# ir03.net
KiCad netlist of a schematic drawn in EAGLE
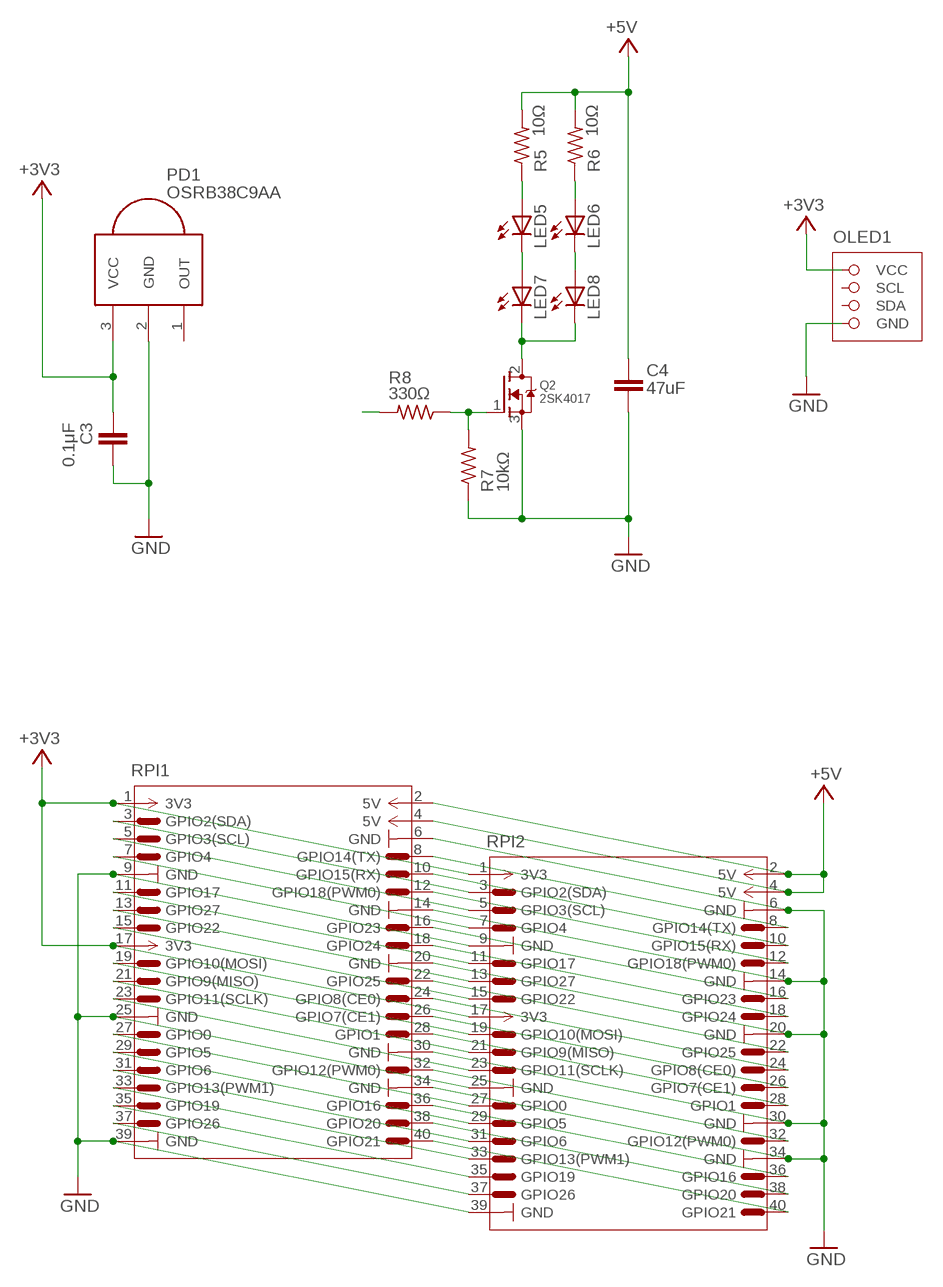
[diagram p0: schematic, sheet 1]

(export (version "E")
  (design (tool "Eeschema 10.0.6"))
  (components
    (comp (ref "C3")
      (value "0.1μF")
      (footprint "eagle-import:C025-025X050")
      (libsource (lib "eagle-import") (part "C-EU025-025X050"))
    )
    (comp (ref "C4")
      (value "47uF")
      (footprint "eagle-import:C025-025X050")
      (libsource (lib "eagle-import") (part "C-EU025-025X050"))
    )
    (comp (ref "LED5")
      (value "LED3MM")
      (footprint "eagle-import:LED3MM")
      (libsource (lib "eagle-import") (part "LED3MM"))
    )
    (comp (ref "LED6")
      (value "LED3MM")
      (footprint "eagle-import:LED3MM")
      (libsource (lib "eagle-import") (part "LED3MM"))
    )
    (comp (ref "LED7")
      (value "LED3MM")
      (footprint "eagle-import:LED3MM")
      (libsource (lib "eagle-import") (part "LED3MM"))
    )
    (comp (ref "LED8")
      (value "LED3MM")
      (footprint "eagle-import:LED3MM")
      (libsource (lib "eagle-import") (part "LED3MM"))
    )
    (comp (ref "OLED1")
      (value "OLED-SSD1306-0.96")
      (footprint "eagle-import:OLED-I2C-0.96")
      (libsource (lib "eagle-import") (part "OLED-SSD1306-0.96"))
    )
    (comp (ref "PD1")
      (value "OSRB38C9AA")
      (footprint "eagle-import:PNA460XM")
      (libsource (lib "eagle-import") (part "PNA460XM"))
    )
    (comp (ref "Q2")
      (value "2SK4017")
      (footprint "eagle-import:TO220V")
      (libsource (lib "eagle-import") (part "MOSFET-NGDS_TO220V"))
    )
    (comp (ref "R5")
      (value "10Ω")
      (footprint "eagle-import:0204_5")
      (libsource (lib "eagle-import") (part "R-US_0204/5"))
    )
    (comp (ref "R6")
      (value "10Ω")
      (footprint "eagle-import:0204_5")
      (libsource (lib "eagle-import") (part "R-US_0204/5"))
    )
    (comp (ref "R7")
      (value "10kΩ")
      (footprint "eagle-import:0204_5")
      (libsource (lib "eagle-import") (part "R-US_0204/5"))
    )
    (comp (ref "R8")
      (value "330Ω")
      (footprint "eagle-import:0204_5")
      (libsource (lib "eagle-import") (part "R-US_0204/5"))
    )
    (comp (ref "RPI1")
      (value "RPI-PIN")
      (footprint "eagle-import:RPI-PIN")
      (libsource (lib "eagle-import") (part "RPI-PIN"))
    )
    (comp (ref "RPI2")
      (value "RPI-PIN")
      (footprint "eagle-import:RPI-PIN")
      (libsource (lib "eagle-import") (part "RPI-PIN"))
    )
  )
  (nets
    (net (code "1") (name "+3V3") (class "Default")
      (node (ref "C3") (pin "1") (pinfunction "1_1") (pintype "passive"))
      (node (ref "OLED1") (pin "VCC") (pinfunction "VCC_VCC") (pintype "bidirectional"))
      (node (ref "PD1") (pin "3") (pinfunction "VCC_3") (pintype "power_in"))
      (node (ref "RPI1") (pin "1") (pinfunction "3V3_1") (pintype "passive"))
      (node (ref "RPI1") (pin "17") (pinfunction "3V3_17") (pintype "passive"))
      (node (ref "RPI2") (pin "1") (pinfunction "3V3_1") (pintype "passive"))
      (node (ref "RPI2") (pin "17") (pinfunction "3V3_17") (pintype "passive"))
    )
    (net (code "2") (name "+5V") (class "Default")
      (node (ref "C4") (pin "1") (pinfunction "1_1") (pintype "passive"))
      (node (ref "R5") (pin "2") (pinfunction "2_2") (pintype "passive"))
      (node (ref "R6") (pin "2") (pinfunction "2_2") (pintype "passive"))
      (node (ref "RPI1") (pin "2") (pinfunction "5V_2") (pintype "passive"))
      (node (ref "RPI1") (pin "4") (pinfunction "5V_4") (pintype "passive"))
      (node (ref "RPI2") (pin "2") (pinfunction "5V_2") (pintype "passive"))
      (node (ref "RPI2") (pin "4") (pinfunction "5V_4") (pintype "passive"))
    )
    (net (code "3") (name "GND") (class "Default")
      (node (ref "C3") (pin "2") (pinfunction "2_2") (pintype "passive"))
      (node (ref "C4") (pin "2") (pinfunction "2_2") (pintype "passive"))
      (node (ref "OLED1") (pin "GND") (pinfunction "GND_GND") (pintype "bidirectional"))
      (node (ref "PD1") (pin "2") (pinfunction "GND_2") (pintype "power_in"))
      (node (ref "Q2") (pin "3") (pinfunction "S_3") (pintype "bidirectional"))
      (node (ref "R7") (pin "1") (pinfunction "1_1") (pintype "passive"))
      (node (ref "RPI1") (pin "14") (pinfunction "GND_14") (pintype "passive"))
      (node (ref "RPI1") (pin "20") (pinfunction "GND_20") (pintype "passive"))
      (node (ref "RPI1") (pin "25") (pinfunction "GND_25") (pintype "passive"))
      (node (ref "RPI1") (pin "30") (pinfunction "GND_30") (pintype "passive"))
      (node (ref "RPI1") (pin "34") (pinfunction "GND_34") (pintype "passive"))
      (node (ref "RPI1") (pin "39") (pinfunction "GND_39") (pintype "passive"))
      (node (ref "RPI1") (pin "6") (pinfunction "GND_6") (pintype "passive"))
      (node (ref "RPI1") (pin "9") (pinfunction "GND_9") (pintype "passive"))
      (node (ref "RPI2") (pin "14") (pinfunction "GND_14") (pintype "passive"))
      (node (ref "RPI2") (pin "20") (pinfunction "GND_20") (pintype "passive"))
      (node (ref "RPI2") (pin "25") (pinfunction "GND_25") (pintype "passive"))
      (node (ref "RPI2") (pin "30") (pinfunction "GND_30") (pintype "passive"))
      (node (ref "RPI2") (pin "34") (pinfunction "GND_34") (pintype "passive"))
      (node (ref "RPI2") (pin "39") (pinfunction "GND_39") (pintype "passive"))
      (node (ref "RPI2") (pin "6") (pinfunction "GND_6") (pintype "passive"))
      (node (ref "RPI2") (pin "9") (pinfunction "GND_9") (pintype "passive"))
    )
    (net (code "4") (name "Net-(LED5-C)") (class "Default")
      (node (ref "LED5") (pin "K") (pinfunction "C_K") (pintype "passive"))
      (node (ref "LED7") (pin "A") (pinfunction "A_A") (pintype "passive"))
    )
    (net (code "5") (name "Net-(LED5-PadA)") (class "Default")
      (node (ref "LED5") (pin "A") (pinfunction "A_A") (pintype "passive"))
      (node (ref "R5") (pin "1") (pinfunction "1_1") (pintype "passive"))
    )
    (net (code "6") (name "Net-(LED6-C)") (class "Default")
      (node (ref "LED6") (pin "K") (pinfunction "C_K") (pintype "passive"))
      (node (ref "LED8") (pin "A") (pinfunction "A_A") (pintype "passive"))
    )
    (net (code "7") (name "Net-(LED6-PadA)") (class "Default")
      (node (ref "LED6") (pin "A") (pinfunction "A_A") (pintype "passive"))
      (node (ref "R6") (pin "1") (pinfunction "1_1") (pintype "passive"))
    )
    (net (code "8") (name "Net-(LED7-C)") (class "Default")
      (node (ref "LED7") (pin "K") (pinfunction "C_K") (pintype "passive"))
      (node (ref "LED8") (pin "K") (pinfunction "C_K") (pintype "passive"))
      (node (ref "Q2") (pin "2") (pinfunction "D_2") (pintype "bidirectional"))
    )
    (net (code "9") (name "Net-(Q2-G)") (class "Default")
      (node (ref "Q2") (pin "1") (pinfunction "G_1") (pintype "bidirectional"))
      (node (ref "R7") (pin "2") (pinfunction "2_2") (pintype "passive"))
      (node (ref "R8") (pin "1") (pinfunction "1_1") (pintype "passive"))
    )
    (net (code "10") (name "Net-(RPI1-GPIO0)") (class "Default")
      (node (ref "RPI1") (pin "27") (pinfunction "GPIO0_27") (pintype "passive"))
      (node (ref "RPI2") (pin "27") (pinfunction "GPIO0_27") (pintype "passive"))
    )
    (net (code "11") (name "Net-(RPI1-GPIO1)") (class "Default")
      (node (ref "RPI1") (pin "28") (pinfunction "GPIO1_28") (pintype "passive"))
      (node (ref "RPI2") (pin "28") (pinfunction "GPIO1_28") (pintype "passive"))
    )
    (net (code "12") (name "Net-(RPI1-GPIO2(SDA))") (class "Default")
      (node (ref "RPI1") (pin "3") (pinfunction "GPIO2(SDA)_3") (pintype "passive"))
      (node (ref "RPI2") (pin "3") (pinfunction "GPIO2(SDA)_3") (pintype "passive"))
    )
    (net (code "13") (name "Net-(RPI1-GPIO3(SCL))") (class "Default")
      (node (ref "RPI1") (pin "5") (pinfunction "GPIO3(SCL)_5") (pintype "passive"))
      (node (ref "RPI2") (pin "5") (pinfunction "GPIO3(SCL)_5") (pintype "passive"))
    )
    (net (code "14") (name "Net-(RPI1-GPIO4)") (class "Default")
      (node (ref "RPI1") (pin "7") (pinfunction "GPIO4_7") (pintype "passive"))
      (node (ref "RPI2") (pin "7") (pinfunction "GPIO4_7") (pintype "passive"))
    )
    (net (code "15") (name "Net-(RPI1-GPIO5)") (class "Default")
      (node (ref "RPI1") (pin "29") (pinfunction "GPIO5_29") (pintype "passive"))
      (node (ref "RPI2") (pin "29") (pinfunction "GPIO5_29") (pintype "passive"))
    )
    (net (code "16") (name "Net-(RPI1-GPIO6)") (class "Default")
      (node (ref "RPI1") (pin "31") (pinfunction "GPIO6_31") (pintype "passive"))
      (node (ref "RPI2") (pin "31") (pinfunction "GPIO6_31") (pintype "passive"))
    )
    (net (code "17") (name "Net-(RPI1-GPIO7(CE1))") (class "Default")
      (node (ref "RPI1") (pin "26") (pinfunction "GPIO7(CE1)_26") (pintype "passive"))
      (node (ref "RPI2") (pin "26") (pinfunction "GPIO7(CE1)_26") (pintype "passive"))
    )
    (net (code "18") (name "Net-(RPI1-GPIO8(CE0))") (class "Default")
      (node (ref "RPI1") (pin "24") (pinfunction "GPIO8(CE0)_24") (pintype "passive"))
      (node (ref "RPI2") (pin "24") (pinfunction "GPIO8(CE0)_24") (pintype "passive"))
    )
    (net (code "19") (name "Net-(RPI1-GPIO9(MISO))") (class "Default")
      (node (ref "RPI1") (pin "21") (pinfunction "GPIO9(MISO)_21") (pintype "passive"))
      (node (ref "RPI2") (pin "21") (pinfunction "GPIO9(MISO)_21") (pintype "passive"))
    )
    (net (code "20") (name "Net-(RPI1-GPIO10(MOSI))") (class "Default")
      (node (ref "RPI1") (pin "19") (pinfunction "GPIO10(MOSI)_19") (pintype "passive"))
      (node (ref "RPI2") (pin "19") (pinfunction "GPIO10(MOSI)_19") (pintype "passive"))
    )
    (net (code "21") (name "Net-(RPI1-GPIO11(SCLK))") (class "Default")
      (node (ref "RPI1") (pin "23") (pinfunction "GPIO11(SCLK)_23") (pintype "passive"))
      (node (ref "RPI2") (pin "23") (pinfunction "GPIO11(SCLK)_23") (pintype "passive"))
    )
    (net (code "22") (name "Net-(RPI1-GPIO12(PWM0))") (class "Default")
      (node (ref "RPI1") (pin "32") (pinfunction "GPIO12(PWM0)_32") (pintype "passive"))
      (node (ref "RPI2") (pin "32") (pinfunction "GPIO12(PWM0)_32") (pintype "passive"))
    )
    (net (code "23") (name "Net-(RPI1-GPIO13(PWM1))") (class "Default")
      (node (ref "RPI1") (pin "33") (pinfunction "GPIO13(PWM1)_33") (pintype "passive"))
      (node (ref "RPI2") (pin "33") (pinfunction "GPIO13(PWM1)_33") (pintype "passive"))
    )
    (net (code "24") (name "Net-(RPI1-GPIO14(TX))") (class "Default")
      (node (ref "RPI1") (pin "8") (pinfunction "GPIO14(TX)_8") (pintype "passive"))
      (node (ref "RPI2") (pin "8") (pinfunction "GPIO14(TX)_8") (pintype "passive"))
    )
    (net (code "25") (name "Net-(RPI1-GPIO15(RX))") (class "Default")
      (node (ref "RPI1") (pin "10") (pinfunction "GPIO15(RX)_10") (pintype "passive"))
      (node (ref "RPI2") (pin "10") (pinfunction "GPIO15(RX)_10") (pintype "passive"))
    )
    (net (code "26") (name "Net-(RPI1-GPIO16)") (class "Default")
      (node (ref "RPI1") (pin "36") (pinfunction "GPIO16_36") (pintype "passive"))
      (node (ref "RPI2") (pin "36") (pinfunction "GPIO16_36") (pintype "passive"))
    )
    (net (code "27") (name "Net-(RPI1-GPIO17)") (class "Default")
      (node (ref "RPI1") (pin "11") (pinfunction "GPIO17_11") (pintype "passive"))
      (node (ref "RPI2") (pin "11") (pinfunction "GPIO17_11") (pintype "passive"))
    )
    (net (code "28") (name "Net-(RPI1-GPIO18(PWM0))") (class "Default")
      (node (ref "RPI1") (pin "12") (pinfunction "GPIO18(PWM0)_12") (pintype "passive"))
      (node (ref "RPI2") (pin "12") (pinfunction "GPIO18(PWM0)_12") (pintype "passive"))
    )
    (net (code "29") (name "Net-(RPI1-GPIO19)") (class "Default")
      (node (ref "RPI1") (pin "35") (pinfunction "GPIO19_35") (pintype "passive"))
      (node (ref "RPI2") (pin "35") (pinfunction "GPIO19_35") (pintype "passive"))
    )
    (net (code "30") (name "Net-(RPI1-GPIO20)") (class "Default")
      (node (ref "RPI1") (pin "38") (pinfunction "GPIO20_38") (pintype "passive"))
      (node (ref "RPI2") (pin "38") (pinfunction "GPIO20_38") (pintype "passive"))
    )
    (net (code "31") (name "Net-(RPI1-GPIO21)") (class "Default")
      (node (ref "RPI1") (pin "40") (pinfunction "GPIO21_40") (pintype "passive"))
      (node (ref "RPI2") (pin "40") (pinfunction "GPIO21_40") (pintype "passive"))
    )
    (net (code "32") (name "Net-(RPI1-GPIO22)") (class "Default")
      (node (ref "RPI1") (pin "15") (pinfunction "GPIO22_15") (pintype "passive"))
      (node (ref "RPI2") (pin "15") (pinfunction "GPIO22_15") (pintype "passive"))
    )
    (net (code "33") (name "Net-(RPI1-GPIO23)") (class "Default")
      (node (ref "RPI1") (pin "16") (pinfunction "GPIO23_16") (pintype "passive"))
      (node (ref "RPI2") (pin "16") (pinfunction "GPIO23_16") (pintype "passive"))
    )
    (net (code "34") (name "Net-(RPI1-GPIO24)") (class "Default")
      (node (ref "RPI1") (pin "18") (pinfunction "GPIO24_18") (pintype "passive"))
      (node (ref "RPI2") (pin "18") (pinfunction "GPIO24_18") (pintype "passive"))
    )
    (net (code "35") (name "Net-(RPI1-GPIO25)") (class "Default")
      (node (ref "RPI1") (pin "22") (pinfunction "GPIO25_22") (pintype "passive"))
      (node (ref "RPI2") (pin "22") (pinfunction "GPIO25_22") (pintype "passive"))
    )
    (net (code "36") (name "Net-(RPI1-GPIO26)") (class "Default")
      (node (ref "RPI1") (pin "37") (pinfunction "GPIO26_37") (pintype "passive"))
      (node (ref "RPI2") (pin "37") (pinfunction "GPIO26_37") (pintype "passive"))
    )
    (net (code "37") (name "Net-(RPI1-GPIO27)") (class "Default")
      (node (ref "RPI1") (pin "13") (pinfunction "GPIO27_13") (pintype "passive"))
      (node (ref "RPI2") (pin "13") (pinfunction "GPIO27_13") (pintype "passive"))
    )
    (net (code "38") (name "unconnected-(OLED1-PadSCL)") (class "Default")
      (node (ref "OLED1") (pin "SCL") (pinfunction "SCL_SCL") (pintype "bidirectional"))
    )
    (net (code "39") (name "unconnected-(OLED1-PadSDA)") (class "Default")
      (node (ref "OLED1") (pin "SDA") (pinfunction "SDA_SDA") (pintype "bidirectional"))
    )
    (net (code "40") (name "unconnected-(PD1-OUT-Pad1)") (class "Default")
      (node (ref "PD1") (pin "1") (pinfunction "OUT_1") (pintype "output"))
    )
    (net (code "41") (name "unconnected-(R8-Pad2)") (class "Default")
      (node (ref "R8") (pin "2") (pinfunction "2_2") (pintype "passive"))
    )
  )
)
